# Battery_Interface.net
KiCad netlist of a schematic drawn in Altium Designer
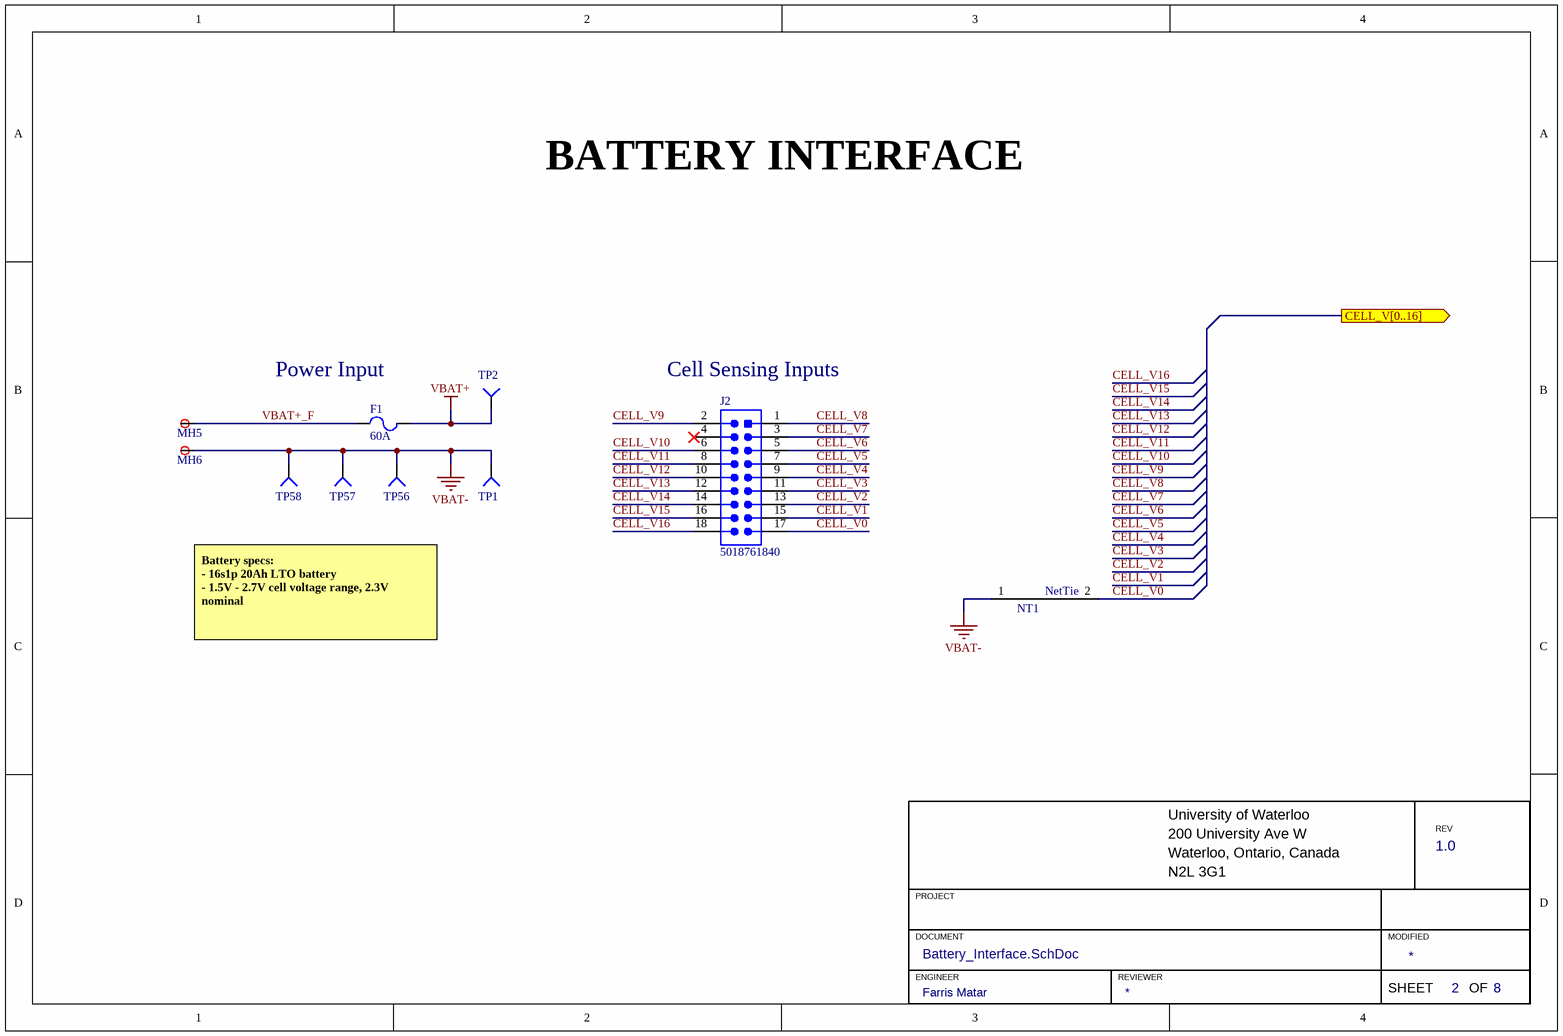
[diagram p0: Battery_Interface.SchDoc]

(export (version "E")
  (design (tool "Eeschema 10.0.6"))
  (components
    (comp (ref "F1")
      (value "FUSE_60A_LITTLEFUSE")
      (footprint "FUSE_456SDE_LITTLEFUSE")
      (description "FUSE BRD MT 60A 250VAC 80VDC SMD")
      (fields (field (name "CURRENT RATING") "60A"))
      (libsource (lib "Personal_Schematic_Library_2022") (part "FUSE_60A_LITTLEFUSE"))
    )
    (comp (ref "J2")
      (value "5018761840")
      (footprint "MOLEX-IGRID 9X2 THRA")
      (description "CONN HEADER R/A 18POS 2MM")
      (fields (field (name "MANUFACTURER PART NUMBER 1") "5018761840"))
      (libsource (lib "Personal_Schematic_Library_2022") (part "CON_MOLEX-IGRID_9x2_THRA"))
    )
    (comp (ref "MH5")
      (value "MOUNTING_HOLE_M5")
      (footprint "MOUNTING_HOLE_5mm")
      (libsource (lib "Personal_Schematic_Library_2022") (part "MOUNTING_HOLE_M5"))
    )
    (comp (ref "MH6")
      (value "MOUNTING_HOLE_M5")
      (footprint "MOUNTING_HOLE_5mm")
      (libsource (lib "Personal_Schematic_Library_2022") (part "MOUNTING_HOLE_M5"))
    )
    (comp (ref "NT1")
      (value "NetTie")
      (footprint "NET_TIE")
      (libsource (lib "Personal_Schematic_Library_2022") (part "NetTie"))
    )
    (comp (ref "TP1")
      (value "TESTPOINT_SMD_LOOP")
      (footprint "S1751-46R")
      (description "TESTPOINT SMD LOOP")
      (libsource (lib "UWRT_Schematic_Library_2020") (part "TESTPOINT_SMD_LOOP"))
    )
    (comp (ref "TP2")
      (value "TESTPOINT_SMD_LOOP")
      (footprint "S1751-46R")
      (description "TESTPOINT SMD LOOP")
      (libsource (lib "UWRT_Schematic_Library_2020") (part "TESTPOINT_SMD_LOOP"))
    )
    (comp (ref "TP56")
      (value "TESTPOINT_SMD_LOOP")
      (footprint "S1751-46R")
      (description "TESTPOINT SMD LOOP")
      (libsource (lib "UWRT_Schematic_Library_2020") (part "TESTPOINT_SMD_LOOP"))
    )
    (comp (ref "TP57")
      (value "TESTPOINT_SMD_LOOP")
      (footprint "S1751-46R")
      (description "TESTPOINT SMD LOOP")
      (libsource (lib "UWRT_Schematic_Library_2020") (part "TESTPOINT_SMD_LOOP"))
    )
    (comp (ref "TP58")
      (value "TESTPOINT_SMD_LOOP")
      (footprint "S1751-46R")
      (description "TESTPOINT SMD LOOP")
      (libsource (lib "UWRT_Schematic_Library_2020") (part "TESTPOINT_SMD_LOOP"))
    )
  )
  (nets
    (net (code "1") (name "/CELL_V0") (class "Default")
      (node (ref "J2") (pin "17") (pinfunction "17_17") (pintype "passive"))
      (node (ref "NT1") (pin "2") (pinfunction "2_2") (pintype "passive"))
    )
    (net (code "2") (name "/CELL_V1") (class "Default")
      (node (ref "J2") (pin "15") (pinfunction "15_15") (pintype "passive"))
    )
    (net (code "3") (name "/CELL_V2") (class "Default")
      (node (ref "J2") (pin "13") (pinfunction "13_13") (pintype "passive"))
    )
    (net (code "4") (name "/CELL_V3") (class "Default")
      (node (ref "J2") (pin "11") (pinfunction "11_11") (pintype "passive"))
    )
    (net (code "5") (name "/CELL_V4") (class "Default")
      (node (ref "J2") (pin "9") (pinfunction "9_9") (pintype "passive"))
    )
    (net (code "6") (name "/CELL_V5") (class "Default")
      (node (ref "J2") (pin "7") (pinfunction "7_7") (pintype "passive"))
    )
    (net (code "7") (name "/CELL_V6") (class "Default")
      (node (ref "J2") (pin "5") (pinfunction "5_5") (pintype "passive"))
    )
    (net (code "8") (name "/CELL_V7") (class "Default")
      (node (ref "J2") (pin "3") (pinfunction "3_3") (pintype "passive"))
    )
    (net (code "9") (name "/CELL_V8") (class "Default")
      (node (ref "J2") (pin "1") (pinfunction "1_1") (pintype "passive"))
    )
    (net (code "10") (name "/CELL_V9") (class "Default")
      (node (ref "J2") (pin "2") (pinfunction "2_2") (pintype "passive"))
    )
    (net (code "11") (name "/CELL_V10") (class "Default")
      (node (ref "J2") (pin "6") (pinfunction "6_6") (pintype "passive"))
    )
    (net (code "12") (name "/CELL_V11") (class "Default")
      (node (ref "J2") (pin "8") (pinfunction "8_8") (pintype "passive"))
    )
    (net (code "13") (name "/CELL_V12") (class "Default")
      (node (ref "J2") (pin "10") (pinfunction "10_10") (pintype "passive"))
    )
    (net (code "14") (name "/CELL_V13") (class "Default")
      (node (ref "J2") (pin "12") (pinfunction "12_12") (pintype "passive"))
    )
    (net (code "15") (name "/CELL_V14") (class "Default")
      (node (ref "J2") (pin "14") (pinfunction "14_14") (pintype "passive"))
    )
    (net (code "16") (name "/CELL_V15") (class "Default")
      (node (ref "J2") (pin "16") (pinfunction "16_16") (pintype "passive"))
    )
    (net (code "17") (name "/CELL_V16") (class "Default")
      (node (ref "J2") (pin "18") (pinfunction "18_18") (pintype "passive"))
    )
    (net (code "19") (name "/VBAT+_F") (class "Default")
      (node (ref "F1") (pin "1") (pinfunction "1_1") (pintype "passive"))
      (node (ref "MH5") (pin "0") (pinfunction "0_0") (pintype "passive"))
    )
    (net (code "20") (name "VBAT+") (class "Default")
      (node (ref "F1") (pin "2") (pinfunction "2_2") (pintype "passive"))
      (node (ref "TP2") (pin "1") (pinfunction "=value_1") (pintype "passive"))
    )
    (net (code "21") (name "VBAT-") (class "Default")
      (node (ref "MH6") (pin "0") (pinfunction "0_0") (pintype "passive"))
      (node (ref "NT1") (pin "1") (pinfunction "1_1") (pintype "passive"))
      (node (ref "TP1") (pin "1") (pinfunction "=value_1") (pintype "passive"))
      (node (ref "TP56") (pin "1") (pinfunction "=value_1") (pintype "passive"))
      (node (ref "TP57") (pin "1") (pinfunction "=value_1") (pintype "passive"))
      (node (ref "TP58") (pin "1") (pinfunction "=value_1") (pintype "passive"))
    )
    (net (code "22") (name "unconnected-(J2-Pad4)") (class "Default")
      (node (ref "J2") (pin "4") (pinfunction "4_4") (pintype "passive+no_connect"))
    )
  )
)
